# Wctrl-v1.net
KiCad netlist of a schematic drawn in Altium Designer
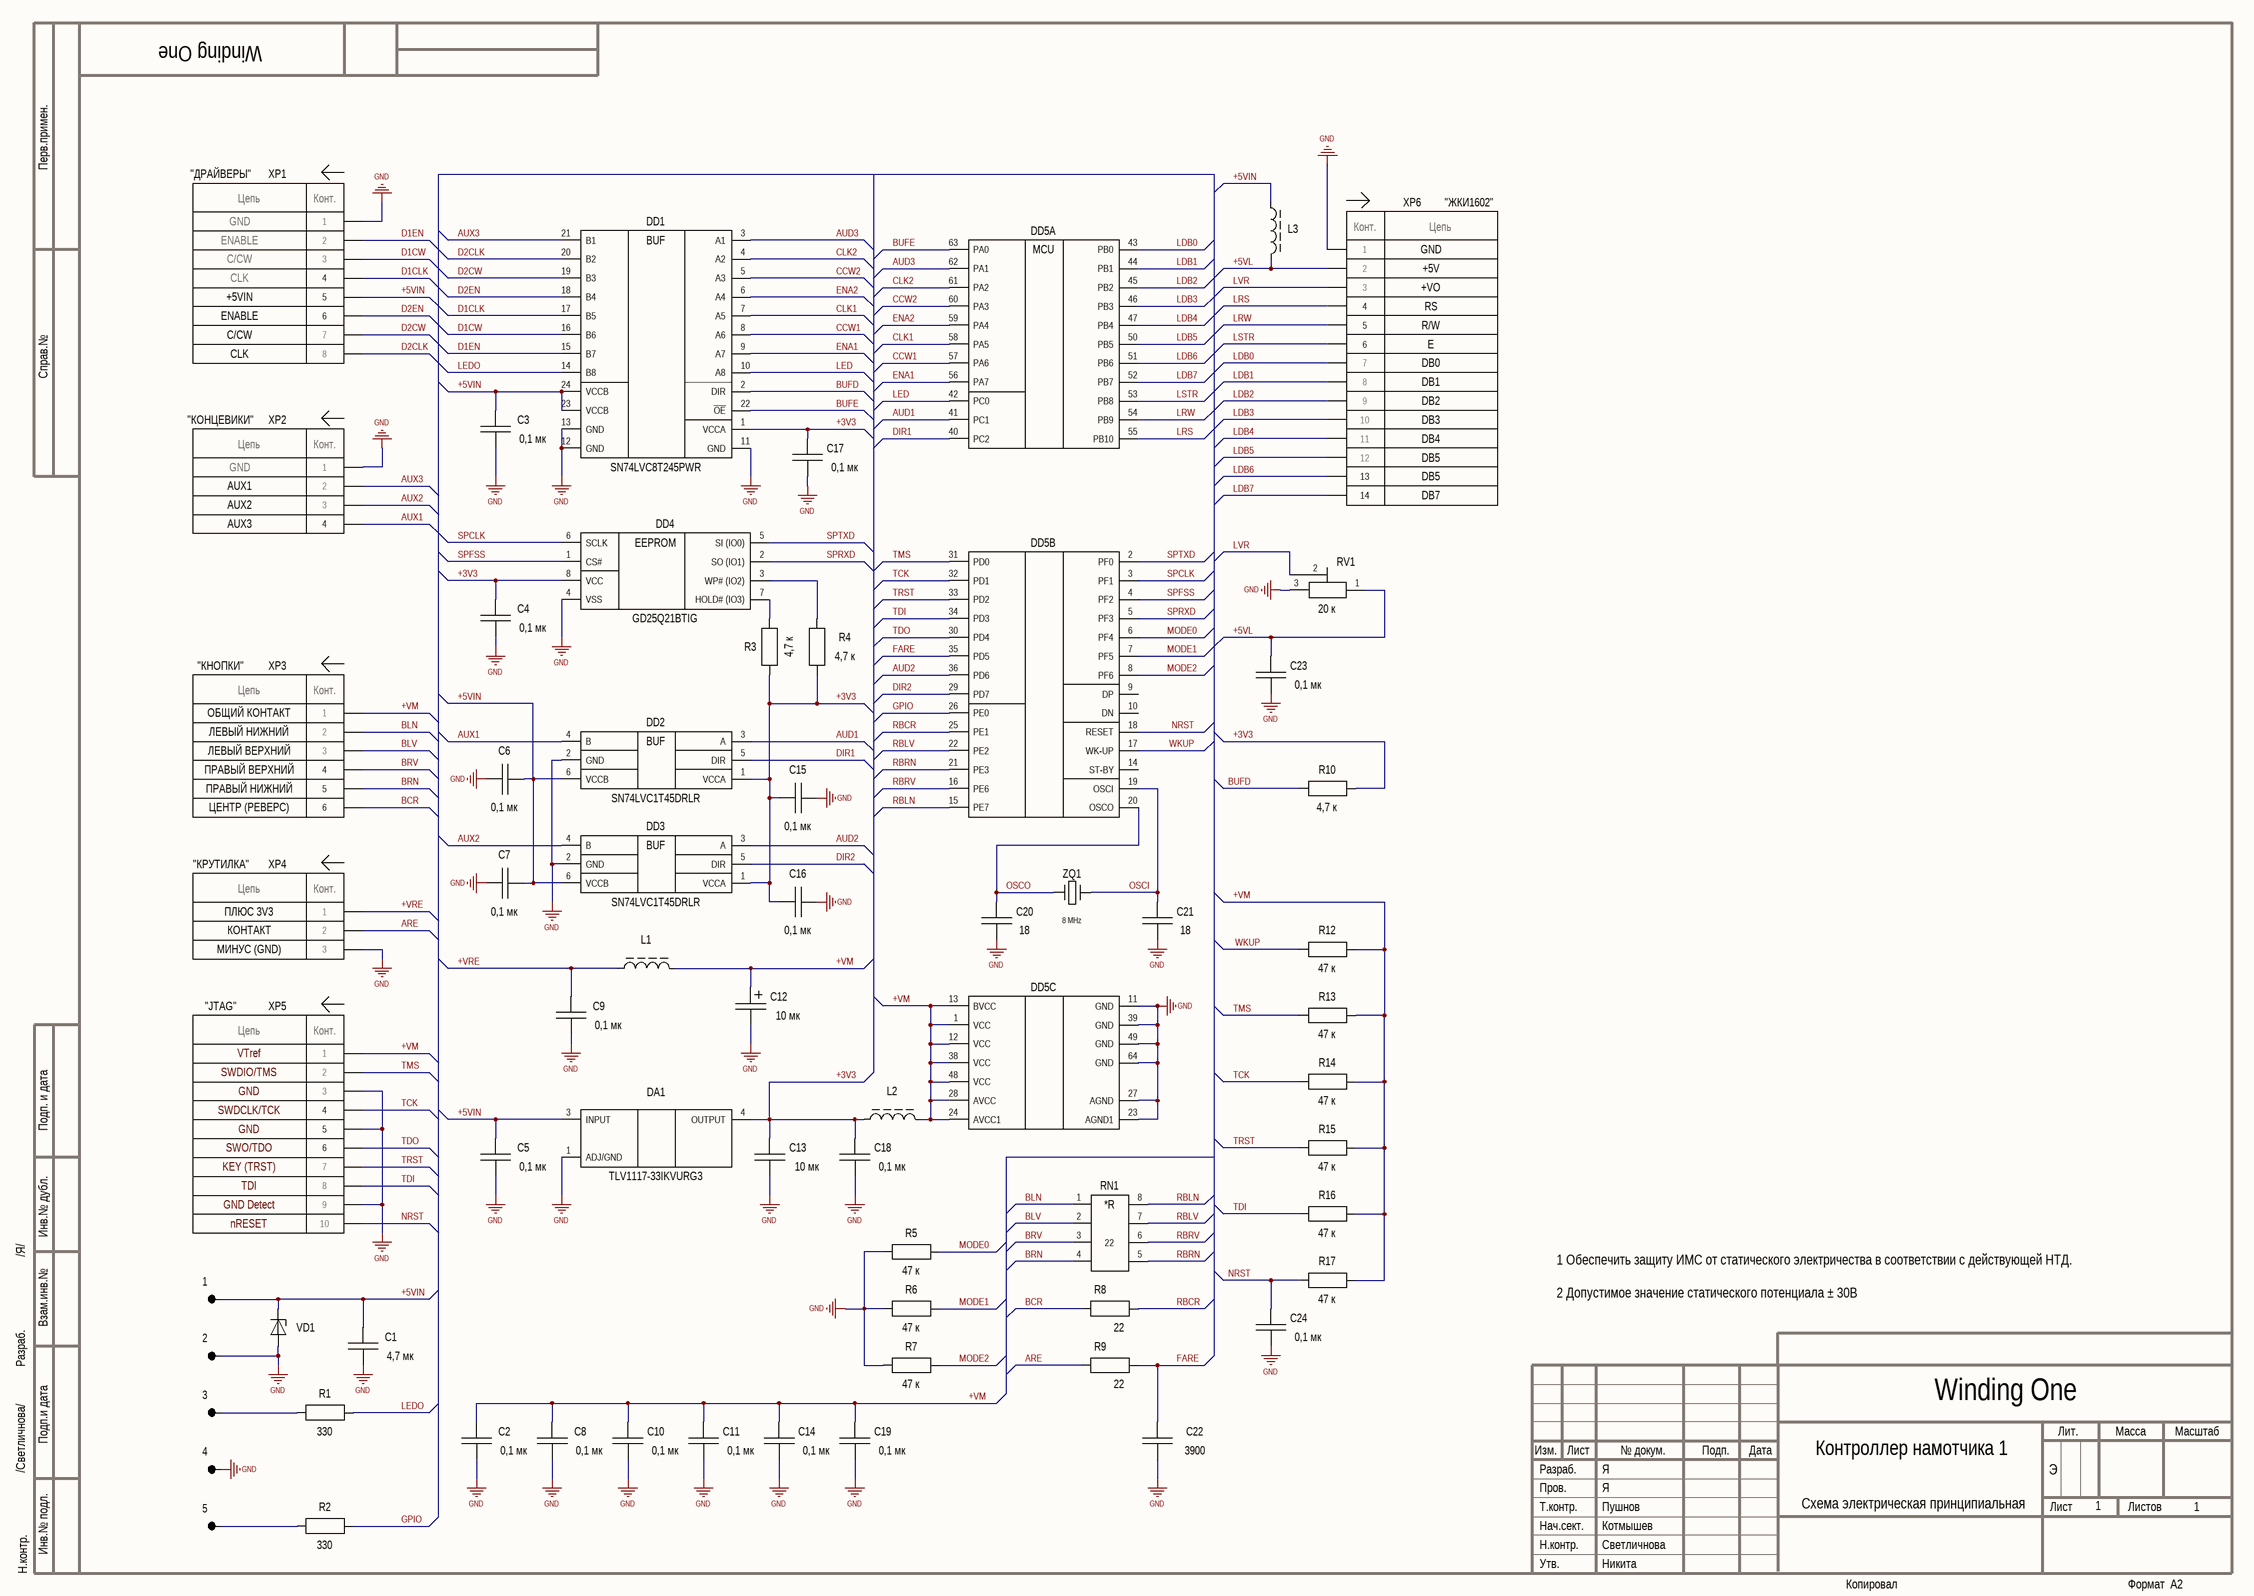
[diagram p0: Wctrl-v1.SchDoc]

(export (version "E")
  (design (tool "Eeschema 10.0.6"))
  (components
    (comp (ref "1")
      (value "Точка пайки")
      (footprint "Pad X 1.0 Round")
      (fields (field (name "PART NUMBER") "Точка п"))
      (libsource (lib "Altium_Base") (part "Точка пайки"))
    )
    (comp (ref "2")
      (value "Точка пайки")
      (footprint "Pad X 1.0 Round")
      (fields (field (name "PART NUMBER") "Точка п"))
      (libsource (lib "Altium_Base") (part "Точка пайки"))
    )
    (comp (ref "3")
      (value "Точка пайки")
      (footprint "Pad X 1.0 Round")
      (fields (field (name "PART NUMBER") "Точка п"))
      (libsource (lib "Altium_Base") (part "Точка пайки"))
    )
    (comp (ref "4")
      (value "Точка пайки")
      (footprint "Pad X 1.0 Round")
      (fields (field (name "PART NUMBER") "Точка п"))
      (libsource (lib "Altium_Base") (part "Точка пайки"))
    )
    (comp (ref "5")
      (value "Точка пайки")
      (footprint "Pad X 1.0 Round")
      (fields (field (name "PART NUMBER") "Точка п"))
      (libsource (lib "Altium_Base") (part "Точка пайки"))
    )
    (comp (ref "C1")
      (value "GRM31CR71E475K")
      (footprint "GRM31C R1")
      (description "10 мкФ ±10% X7R 25В, 1206 (3,2x1,6мм)")
      (fields (field (name "CAPACITANCE") "4,7 мк") (field (name "TOLERANCE") "±10%"))
      (libsource (lib "Altium_Base") (part "Конденсатор"))
    )
    (comp (ref "C2")
      (value "GRM21BR71H104K")
      (footprint "CAPC 0805 T1")
      (description "0,1 мкФ ±10% X7R 50В (2,0х1,25 мм)")
      (fields (field (name "CAPACITANCE") "0,1 мк") (field (name "TOLERANCE") "±10%"))
      (libsource (lib "Altium_Base") (part "Конденсатор"))
    )
    (comp (ref "C3")
      (value "GRM21BR71H104K")
      (footprint "CAPC 0805 T1")
      (description "0,1 мкФ ±10% X7R 50В (2,0х1,25 мм)")
      (fields (field (name "CAPACITANCE") "0,1 мк") (field (name "TOLERANCE") "±10%"))
      (libsource (lib "Altium_Base") (part "Конденсатор"))
    )
    (comp (ref "C4")
      (value "GRM21BR71H104K")
      (footprint "CAPC 0805 T1")
      (description "0,1 мкФ ±10% X7R 50В (2,0х1,25 мм)")
      (fields (field (name "CAPACITANCE") "0,1 мк") (field (name "TOLERANCE") "±10%"))
      (libsource (lib "Altium_Base") (part "Конденсатор"))
    )
    (comp (ref "C5")
      (value "GRM21BR71H104K")
      (footprint "CAPC 0805 T1")
      (description "0,1 мкФ ±10% X7R 50В (2,0х1,25 мм)")
      (fields (field (name "CAPACITANCE") "0,1 мк") (field (name "TOLERANCE") "±10%"))
      (libsource (lib "Altium_Base") (part "Конденсатор"))
    )
    (comp (ref "C6")
      (value "GRM21BR71H104K")
      (footprint "CAPC 0805 T1")
      (description "0,1 мкФ ±10% X7R 50В (2,0х1,25 мм)")
      (fields (field (name "CAPACITANCE") "0,1 мк") (field (name "TOLERANCE") "±10%"))
      (libsource (lib "Altium_Base") (part "Конденсатор"))
    )
    (comp (ref "C7")
      (value "GRM21BR71H104K")
      (footprint "CAPC 0805 T1")
      (description "0,1 мкФ ±10% X7R 50В (2,0х1,25 мм)")
      (fields (field (name "CAPACITANCE") "0,1 мк") (field (name "TOLERANCE") "±10%"))
      (libsource (lib "Altium_Base") (part "Конденсатор"))
    )
    (comp (ref "C8")
      (value "GRM21BR71H104K")
      (footprint "CAPC 0805 T1")
      (description "0,1 мкФ ±10% X7R 50В (2,0х1,25 мм)")
      (fields (field (name "CAPACITANCE") "0,1 мк") (field (name "TOLERANCE") "±10%"))
      (libsource (lib "Altium_Base") (part "Конденсатор"))
    )
    (comp (ref "C9")
      (value "GRM21BR71H104K")
      (footprint "CAPC 0805 T1")
      (description "0,1 мкФ ±10% X7R 50В (2,0х1,25 мм)")
      (fields (field (name "CAPACITANCE") "0,1 мк") (field (name "TOLERANCE") "±10%"))
      (libsource (lib "Altium_Base") (part "Конденсатор"))
    )
    (comp (ref "C10")
      (value "GRM21BR71H104K")
      (footprint "CAPC 0805 T1")
      (description "0,1 мкФ ±10% X7R 50В (2,0х1,25 мм)")
      (fields (field (name "CAPACITANCE") "0,1 мк") (field (name "TOLERANCE") "±10%"))
      (libsource (lib "Altium_Base") (part "Конденсатор"))
    )
    (comp (ref "C11")
      (value "GRM21BR71H104K")
      (footprint "CAPC 0805 T1")
      (description "0,1 мкФ ±10% X7R 50В (2,0х1,25 мм)")
      (fields (field (name "CAPACITANCE") "0,1 мк") (field (name "TOLERANCE") "±10%"))
      (libsource (lib "Altium_Base") (part "Конденсатор"))
    )
    (comp (ref "C12")
      (value "К53-68 \"C\"-20В-10 мкФ±10%")
      (footprint "К53-68-C")
      (description "Танталовый, тип C")
      (fields (field (name "CAPACITANCE") "10 мк") (field (name "TOLERANCE") "±10%"))
      (libsource (lib "Altium_Base") (part "Конд. полярный"))
    )
    (comp (ref "C13")
      (value "GRM31CR71C106K")
      (footprint "GRM31C R1")
      (description "10 мкФ, ±10% X7R 16В, 1206 (3,2x1,6x1,6 мм)")
      (fields (field (name "CAPACITANCE") "10 мк") (field (name "TOLERANCE") "±10%"))
      (libsource (lib "Altium_Base") (part "Конденсатор"))
    )
    (comp (ref "C14")
      (value "GRM21BR71H104K")
      (footprint "CAPC 0805 T1")
      (description "0,1 мкФ ±10% X7R 50В (2,0х1,25 мм)")
      (fields (field (name "CAPACITANCE") "0,1 мк") (field (name "TOLERANCE") "±10%"))
      (libsource (lib "Altium_Base") (part "Конденсатор"))
    )
    (comp (ref "C15")
      (value "GRM21BR71H104K")
      (footprint "CAPC 0805 T1")
      (description "0,1 мкФ ±10% X7R 50В (2,0х1,25 мм)")
      (fields (field (name "CAPACITANCE") "0,1 мк") (field (name "TOLERANCE") "±10%"))
      (libsource (lib "Altium_Base") (part "Конденсатор"))
    )
    (comp (ref "C16")
      (value "GRM21BR71H104K")
      (footprint "CAPC 0805 T1")
      (description "0,1 мкФ ±10% X7R 50В (2,0х1,25 мм)")
      (fields (field (name "CAPACITANCE") "0,1 мк") (field (name "TOLERANCE") "±10%"))
      (libsource (lib "Altium_Base") (part "Конденсатор"))
    )
    (comp (ref "C17")
      (value "GRM21BR71H104K")
      (footprint "CAPC 0805 T1")
      (description "0,1 мкФ ±10% X7R 50В (2,0х1,25 мм)")
      (fields (field (name "CAPACITANCE") "0,1 мк") (field (name "TOLERANCE") "±10%"))
      (libsource (lib "Altium_Base") (part "Конденсатор"))
    )
    (comp (ref "C18")
      (value "GRM21BR71H104K")
      (footprint "CAPC 0805 T1")
      (description "0,1 мкФ ±10% X7R 50В (2,0х1,25 мм)")
      (fields (field (name "CAPACITANCE") "0,1 мк") (field (name "TOLERANCE") "±10%"))
      (libsource (lib "Altium_Base") (part "Конденсатор"))
    )
    (comp (ref "C19")
      (value "GRM21BR71H104K")
      (footprint "CAPC 0805 T1")
      (description "0,1 мкФ ±10% X7R 50В (2,0х1,25 мм)")
      (fields (field (name "CAPACITANCE") "0,1 мк") (field (name "TOLERANCE") "±10%"))
      (libsource (lib "Altium_Base") (part "Конденсатор"))
    )
    (comp (ref "C20")
      (value "GRM1885C1H180J")
      (footprint "CAPC 0603 T1")
      (description "18 пФ ±5% C0G 50В (1,6x0,8мм)")
      (fields (field (name "CAPACITANCE") "18") (field (name "TOLERANCE") "±5%"))
      (libsource (lib "Altium_Base") (part "Конденсатор"))
    )
    (comp (ref "C21")
      (value "GRM1885C1H180J")
      (footprint "CAPC 0603 T1")
      (description "18 пФ ±5% C0G 50В (1,6x0,8мм)")
      (fields (field (name "CAPACITANCE") "18") (field (name "TOLERANCE") "±5%"))
      (libsource (lib "Altium_Base") (part "Конденсатор"))
    )
    (comp (ref "C22")
      (value "GRM2165C1H392J")
      (footprint "CAPC 0805 T1")
      (description "3900 пФ ±5% C0G 50В (2,0х1,25 мм)")
      (fields (field (name "CAPACITANCE") "3900") (field (name "TOLERANCE") "±5%"))
      (libsource (lib "Altium_Base") (part "Конденсатор"))
    )
    (comp (ref "C23")
      (value "GRM21BR71H104K")
      (footprint "CAPC 0805 T1")
      (description "0,1 мкФ ±10% X7R 50В (2,0х1,25 мм)")
      (fields (field (name "CAPACITANCE") "0,1 мк") (field (name "TOLERANCE") "±10%"))
      (libsource (lib "Altium_Base") (part "Конденсатор"))
    )
    (comp (ref "C24")
      (value "GRM21BR71H104K")
      (footprint "CAPC 0805 T1")
      (description "0,1 мкФ ±10% X7R 50В (2,0х1,25 мм)")
      (fields (field (name "CAPACITANCE") "0,1 мк") (field (name "TOLERANCE") "±10%"))
      (libsource (lib "Altium_Base") (part "Конденсатор"))
    )
    (comp (ref "DA1")
      (value "TLV1117-33IKVURG3")
      (footprint "TO-252_TI_KVU (KVU0003A)_R1")
      (description "3,3V Fixed Low-Dropout Voltage Regulator, TO-252")
      (libsource (lib "Altium_Base") (part "TLV1117-KVU"))
    )
    (comp (ref "DD1")
      (value "SN74LVC8T245PWR")
      (footprint "TSSOP24_TI_PW (PW0024A)")
      (description "Dual-Supply Bus Transceiver (8-bit) with 3-State Outputs, TSSOP-24")
      (libsource (lib "Altium_Base") (part "SN74LVC8T245"))
    )
    (comp (ref "DD2")
      (value "SN74LVC1T45DRLR")
      (footprint "SOT-5x3_TI_DRL(R-PDSO-N6)")
      (description "Single-Bit Dual-Supply Bus Transceiver With Configurable Voltage Translation and 3-State Outputs")
      (libsource (lib "Altium_Base") (part "SN74LVC1T45DRLR"))
    )
    (comp (ref "DD3")
      (value "SN74LVC1T45DRLR")
      (footprint "SOT-5x3_TI_DRL(R-PDSO-N6)")
      (description "Single-Bit Dual-Supply Bus Transceiver With Configurable Voltage Translation and 3-State Outputs")
      (libsource (lib "Altium_Base") (part "SN74LVC1T45DRLR"))
    )
    (comp (ref "DD4")
      (value "GD25Q21BTIG")
      (footprint "SOIC-8 IPC N")
      (description "Serial Flash 2M-bit, [SPI x 1 / x 2 / x 4], 3,3V, 104 MHz, SOP8")
      (libsource (lib "Altium_Base") (part "GD25Q21B"))
    )
    (comp (ref "DD5")
      (value "К1986ВЕ92QI")
      (footprint "К1986ВЕ92QI")
      (description "МК, 32-битное ядро ARM Cortex M3 80 МГц, LQFP64")
      (libsource (lib "Altium_Base") (part "К1986ВЕ92QI"))
    )
    (comp (ref "L1")
      (value "Дроссель BLM")
      (footprint "INDC2012X10N")
      (description "Chip Ferrite Bead BLM21_SN series - 200 mA, 470 Ohm (@100 MHz), 0805")
      (fields (field (name "PART NUMBER") "BLM21AG471SN1") (field (name "TOLERANCE") "25%"))
      (libsource (lib "Altium_Base") (part "Дроссель BLM"))
    )
    (comp (ref "L2")
      (value "Дроссель BLM")
      (footprint "INDC2012X10N")
      (description "Chip Ferrite Bead BLM21_SN series - 200 mA, 470 Ohm (@100 MHz), 0805")
      (fields (field (name "PART NUMBER") "BLM21AG471SN1") (field (name "TOLERANCE") "25%"))
      (libsource (lib "Altium_Base") (part "Дроссель BLM"))
    )
    (comp (ref "L3")
      (value "Дроссель BLM")
      (footprint "INDC2012X10N")
      (description "Chip Ferrite Bead BLM21_SN series - 200 mA, 470 Ohm (@100 MHz), 0805")
      (fields (field (name "PART NUMBER") "BLM21AG471SN1") (field (name "TOLERANCE") "25%"))
      (libsource (lib "Altium_Base") (part "Дроссель BLM"))
    )
    (comp (ref "R1")
      (value "Резистор")
      (footprint "IEC 2012N")
      (description "Чип-резистор 0805")
      (fields
        (field (name "PART NUMBER") "Р1-12-0,125-330 Ом±5%-Т")
        (field (name "RESISTANCE") "330")
        (field (name "TOLERANCE") "±5%")
      )
      (libsource (lib "Altium_Base") (part "Резистор"))
    )
    (comp (ref "R2")
      (value "Резистор")
      (footprint "IEC 2012N")
      (description "Чип-резистор 0805")
      (fields
        (field (name "PART NUMBER") "Р1-12-0,125-330 Ом±5%-Т")
        (field (name "RESISTANCE") "330")
        (field (name "TOLERANCE") "±5%")
      )
      (libsource (lib "Altium_Base") (part "Резистор"))
    )
    (comp (ref "R3")
      (value "Резистор")
      (footprint "IEC 2011N")
      (description "Чип-резистор 0603")
      (fields
        (field (name "PART NUMBER") "Р1-12-0,1-4,7 кОм±5%-Т")
        (field (name "RESISTANCE") "4,7 к")
        (field (name "TOLERANCE") "±5%")
      )
      (libsource (lib "Altium_Base") (part "Резистор"))
    )
    (comp (ref "R4")
      (value "Резистор")
      (footprint "IEC 2011N")
      (description "Чип-резистор 0603")
      (fields
        (field (name "PART NUMBER") "Р1-12-0,1-4,7 кОм±5%-Т")
        (field (name "RESISTANCE") "4,7 к")
        (field (name "TOLERANCE") "±5%")
      )
      (libsource (lib "Altium_Base") (part "Резистор"))
    )
    (comp (ref "R5")
      (value "Резистор")
      (footprint "IEC 2011N")
      (description "Чип-резистор 0603")
      (fields
        (field (name "PART NUMBER") "Р1-12-0,1-47 кОм±1%-М")
        (field (name "RESISTANCE") "47 к")
        (field (name "TOLERANCE") "±1%")
      )
      (libsource (lib "Altium_Base") (part "Резистор"))
    )
    (comp (ref "R6")
      (value "Резистор")
      (footprint "IEC 2011N")
      (description "Чип-резистор 0603")
      (fields
        (field (name "PART NUMBER") "Р1-12-0,1-47 кОм±1%-М")
        (field (name "RESISTANCE") "47 к")
        (field (name "TOLERANCE") "±1%")
      )
      (libsource (lib "Altium_Base") (part "Резистор"))
    )
    (comp (ref "R7")
      (value "Резистор")
      (footprint "IEC 2011N")
      (description "Чип-резистор 0603")
      (fields
        (field (name "PART NUMBER") "Р1-12-0,1-47 кОм±1%-М")
        (field (name "RESISTANCE") "47 к")
        (field (name "TOLERANCE") "±1%")
      )
      (libsource (lib "Altium_Base") (part "Резистор"))
    )
    (comp (ref "R8")
      (value "Резистор")
      (footprint "IEC 2011N")
      (description "Чип-резистор 0603")
      (fields
        (field (name "PART NUMBER") "Р1-12-0,1-22 Ом±5%-Т")
        (field (name "RESISTANCE") "22")
        (field (name "TOLERANCE") "±5%")
      )
      (libsource (lib "Altium_Base") (part "Резистор"))
    )
    (comp (ref "R9")
      (value "Резистор")
      (footprint "IEC 2011N")
      (description "Чип-резистор 0603")
      (fields
        (field (name "PART NUMBER") "Р1-12-0,1-22 Ом±5%-Т")
        (field (name "RESISTANCE") "22")
        (field (name "TOLERANCE") "±5%")
      )
      (libsource (lib "Altium_Base") (part "Резистор"))
    )
    (comp (ref "R10")
      (value "Резистор")
      (footprint "IEC 2011N")
      (description "Чип-резистор 0603")
      (fields
        (field (name "PART NUMBER") "Р1-12-0,1-4,7 кОм±5%-Т")
        (field (name "RESISTANCE") "4,7 к")
        (field (name "TOLERANCE") "±5%")
      )
      (libsource (lib "Altium_Base") (part "Резистор"))
    )
    (comp (ref "R12")
      (value "Резистор")
      (footprint "IEC 2011N")
      (description "Чип-резистор 0603")
      (fields
        (field (name "PART NUMBER") "Р1-12-0,1-47 кОм±1%-М")
        (field (name "RESISTANCE") "47 к")
        (field (name "TOLERANCE") "±1%")
      )
      (libsource (lib "Altium_Base") (part "Резистор"))
    )
    (comp (ref "R13")
      (value "Резистор")
      (footprint "IEC 2011N")
      (description "Чип-резистор 0603")
      (fields
        (field (name "PART NUMBER") "Р1-12-0,1-47 кОм±1%-М")
        (field (name "RESISTANCE") "47 к")
        (field (name "TOLERANCE") "±1%")
      )
      (libsource (lib "Altium_Base") (part "Резистор"))
    )
    (comp (ref "R14")
      (value "Резистор")
      (footprint "IEC 2011N")
      (description "Чип-резистор 0603")
      (fields
        (field (name "PART NUMBER") "Р1-12-0,1-47 кОм±1%-М")
        (field (name "RESISTANCE") "47 к")
        (field (name "TOLERANCE") "±1%")
      )
      (libsource (lib "Altium_Base") (part "Резистор"))
    )
    (comp (ref "R15")
      (value "Резистор")
      (footprint "IEC 2011N")
      (description "Чип-резистор 0603")
      (fields
        (field (name "PART NUMBER") "Р1-12-0,1-47 кОм±1%-М")
        (field (name "RESISTANCE") "47 к")
        (field (name "TOLERANCE") "±1%")
      )
      (libsource (lib "Altium_Base") (part "Резистор"))
    )
    (comp (ref "R16")
      (value "Резистор")
      (footprint "IEC 2011N")
      (description "Чип-резистор 0603")
      (fields
        (field (name "PART NUMBER") "Р1-12-0,1-47 кОм±1%-М")
        (field (name "RESISTANCE") "47 к")
        (field (name "TOLERANCE") "±1%")
      )
      (libsource (lib "Altium_Base") (part "Резистор"))
    )
    (comp (ref "R17")
      (value "Резистор")
      (footprint "IEC 2011N")
      (description "Чип-резистор 0603")
      (fields
        (field (name "PART NUMBER") "Р1-12-0,1-47 кОм±1%-М")
        (field (name "RESISTANCE") "47 к")
        (field (name "TOLERANCE") "±1%")
      )
      (libsource (lib "Altium_Base") (part "Резистор"))
    )
    (comp (ref "RN1")
      (value "CAT16-220J4LF")
      (footprint "НР1-2Р V1")
      (description "Набор резисторов 4шт х 22 Ом, 0,0625 Вт , 50В, 5%, SMD 3.2 x 1.6 x 0.8")
      (fields (field (name "RESISTANCE") "22") (field (name "TOLERANCE") "±5%"))
      (libsource (lib "Altium_Base") (part "Резиторов набор 8к"))
    )
    (comp (ref "RV1")
      (value "Резистор подстроечный")
      (footprint "3313J-1")
      (description "Trimming Potentiometer, 20 kOhm, SMD 3.5 x 3.2 x 2.2")
      (fields
        (field (name "PART NUMBER") "3313J-1-203E")
        (field (name "RESISTANCE") "20 к")
        (field (name "TOLERANCE") "±20%")
      )
      (libsource (lib "Altium_Base") (part "Резистор подстроечный"))
    )
    (comp (ref "VD1")
      (value "Стабилитрон")
      (footprint "SMBJ-LF-R1")
      (description "TVS Diode, Uni-directional, 12V, DO-214AA (SMB J-Bend)")
      (fields (field (name "PART NUMBER") "SMBJ12A"))
      (libsource (lib "Altium_Base") (part "Стабилитрон"))
    )
    (comp (ref "XP1")
      (value "X8 Connector XP")
      (footprint "СНП346-8ВП21-1")
      (description "Вилка СНП346 однорядная, прямая, 8 контактов")
      (fields (field (name "НАЗНАЧЕНИЕ") "\"ДРАЙВЕРЫ\"") (field (name "PART NUMBER") "СНП346-8ВП21-1-В"))
      (libsource (lib "Altium_Base") (part "X8 Connector XP"))
    )
    (comp (ref "XP2")
      (value "X4 Connector XP")
      (footprint "СНП346-4ВП21-1")
      (description "Вилка СНП346 однорядная, прямая, 4 контакта")
      (fields (field (name "НАЗНАЧЕНИЕ") "\"КОНЦЕВИКИ\"") (field (name "PART NUMBER") "СНП346-4ВП21-1-В"))
      (libsource (lib "Altium_Base") (part "X4 Connector XP"))
    )
    (comp (ref "XP3")
      (value "X6 Connector XP")
      (footprint "СНП346-6ВП21-1")
      (description "Вилка СНП346 однорядная, прямая, 6 контактов")
      (fields (field (name "НАЗНАЧЕНИЕ") "\"КНОПКИ\"") (field (name "PART NUMBER") "СНП346-6ВП21-1-В"))
      (libsource (lib "Altium_Base") (part "X6 Connector XP"))
    )
    (comp (ref "XP4")
      (value "X3 Connector XP")
      (footprint "СНП346-3ВП21-1")
      (description "Вилка СНП346 однорядная, прямая, 3 контакта")
      (fields (field (name "НАЗНАЧЕНИЕ") "\"КРУТИЛКА\"") (field (name "PART NUMBER") "СНП346-3ВП21-1-В"))
      (libsource (lib "Altium_Base") (part "X3 Connector XP"))
    )
    (comp (ref "XP5")
      (value "X10 Connector XP")
      (footprint "DS1014-10SF1B")
      (description "Вилка двухрядная на плату IDC-2-10, прямая, шаг 2  мм, 10 контактов")
      (fields (field (name "НАЗНАЧЕНИЕ") "\"JTAG\"") (field (name "PART NUMBER") "DS1014-10SF1B"))
      (libsource (lib "Altium_Base") (part "X10 Connector XP"))
    )
    (comp (ref "XP6")
      (value "X14 Connector XP")
      (footprint "DS1025-01-1X14")
      (description "Вилка на плату, прямая, шаг 2,0 мм, 14 контактов")
      (fields (field (name "НАЗНАЧЕНИЕ") "\"ЖКИ1602\"") (field (name "PART NUMBER") "DS1025-01*14P8BV2"))
      (libsource (lib "Altium_Base") (part "X14 Connector XP"))
    )
    (comp (ref "ZQ1")
      (value "Кварц 2к")
      (footprint "HC-49S AS TXC")
      (description "8.000 МHz (Tolerance ±30ppm, Stability ±50ppm, Load Capacitance 12 pF)")
      (fields (field (name "ЧАСТОТА") "8 MHz") (field (name "PART NUMBER") "AS-8.000MAGE"))
      (libsource (lib "Altium_Base") (part "Кварц 2к"))
    )
  )
  (nets
    (net (code "1") (name "/+3V3") (class "Default")
      (node (ref "C13") (pin "2") (pinfunction "2_2") (pintype "passive"))
      (node (ref "C15") (pin "2") (pinfunction "2_2") (pintype "passive"))
      (node (ref "C16") (pin "2") (pinfunction "2_2") (pintype "passive"))
      (node (ref "C17") (pin "2") (pinfunction "2_2") (pintype "passive"))
      (node (ref "C18") (pin "2") (pinfunction "2_2") (pintype "passive"))
      (node (ref "C4") (pin "2") (pinfunction "2_2") (pintype "passive"))
      (node (ref "DA1") (pin "4") (pinfunction "OUTPUT_4") (pintype "passive"))
      (node (ref "DD1") (pin "1") (pinfunction "VCCA_1") (pintype "passive"))
      (node (ref "DD2") (pin "1") (pinfunction "VCCA_1") (pintype "passive"))
      (node (ref "DD3") (pin "1") (pinfunction "VCCA_1") (pintype "passive"))
      (node (ref "DD4") (pin "8") (pinfunction "VCC_8") (pintype "passive"))
      (node (ref "L2") (pin "1") (pinfunction "1_1") (pintype "passive"))
      (node (ref "R10") (pin "2") (pinfunction "2_2") (pintype "passive"))
      (node (ref "R3") (pin "1") (pinfunction "1_1") (pintype "passive"))
      (node (ref "R4") (pin "1") (pinfunction "1_1") (pintype "passive"))
    )
    (net (code "2") (name "/+5VIN") (class "Default")
      (node (ref "1") (pin "1") (pinfunction "1_1") (pintype "passive"))
      (node (ref "C1") (pin "2") (pinfunction "2_2") (pintype "passive"))
      (node (ref "C3") (pin "2") (pinfunction "2_2") (pintype "passive"))
      (node (ref "C5") (pin "2") (pinfunction "2_2") (pintype "passive"))
      (node (ref "C6") (pin "1") (pinfunction "1_1") (pintype "passive"))
      (node (ref "C7") (pin "1") (pinfunction "1_1") (pintype "passive"))
      (node (ref "DA1") (pin "3") (pinfunction "INPUT_3") (pintype "passive"))
      (node (ref "DD1") (pin "23") (pinfunction "VCCB_23") (pintype "passive"))
      (node (ref "DD1") (pin "24") (pinfunction "VCCB_24") (pintype "passive"))
      (node (ref "DD2") (pin "6") (pinfunction "VCCB_6") (pintype "passive"))
      (node (ref "DD3") (pin "6") (pinfunction "VCCB_6") (pintype "passive"))
      (node (ref "L3") (pin "1") (pinfunction "1_1") (pintype "passive"))
      (node (ref "VD1") (pin "1") (pinfunction "Катод_1") (pintype "passive"))
      (node (ref "XP1") (pin "5") (pinfunction "5_5") (pintype "passive"))
    )
    (net (code "3") (name "/+5VL") (class "Default")
      (node (ref "C23") (pin "2") (pinfunction "2_2") (pintype "passive"))
      (node (ref "L3") (pin "2") (pinfunction "2_2") (pintype "passive"))
      (node (ref "RV1") (pin "1") (pinfunction "1_1") (pintype "passive"))
      (node (ref "XP6") (pin "2") (pinfunction "2_2") (pintype "passive"))
    )
    (net (code "4") (name "/+VM") (class "Default")
      (node (ref "C10") (pin "2") (pinfunction "2_2") (pintype "passive"))
      (node (ref "C11") (pin "2") (pinfunction "2_2") (pintype "passive"))
      (node (ref "C12") (pin "1") (pinfunction "1_1") (pintype "passive"))
      (node (ref "C14") (pin "2") (pinfunction "2_2") (pintype "passive"))
      (node (ref "C19") (pin "2") (pinfunction "2_2") (pintype "passive"))
      (node (ref "C2") (pin "2") (pinfunction "2_2") (pintype "passive"))
      (node (ref "C8") (pin "2") (pinfunction "2_2") (pintype "passive"))
      (node (ref "DD5") (pin "1") (pinfunction "VCC_1") (pintype "passive"))
      (node (ref "DD5") (pin "12") (pinfunction "VCC_12") (pintype "passive"))
      (node (ref "DD5") (pin "13") (pinfunction "BVCC_13") (pintype "passive"))
      (node (ref "DD5") (pin "24") (pinfunction "AVCC1_24") (pintype "passive"))
      (node (ref "DD5") (pin "28") (pinfunction "AVCC_28") (pintype "passive"))
      (node (ref "DD5") (pin "38") (pinfunction "VCC_38") (pintype "passive"))
      (node (ref "DD5") (pin "48") (pinfunction "VCC_48") (pintype "passive"))
      (node (ref "L1") (pin "2") (pinfunction "2_2") (pintype "passive"))
      (node (ref "L2") (pin "2") (pinfunction "2_2") (pintype "passive"))
      (node (ref "R12") (pin "2") (pinfunction "2_2") (pintype "passive"))
      (node (ref "R13") (pin "2") (pinfunction "2_2") (pintype "passive"))
      (node (ref "R14") (pin "2") (pinfunction "2_2") (pintype "passive"))
      (node (ref "R15") (pin "2") (pinfunction "2_2") (pintype "passive"))
      (node (ref "R16") (pin "2") (pinfunction "2_2") (pintype "passive"))
      (node (ref "R17") (pin "2") (pinfunction "2_2") (pintype "passive"))
      (node (ref "XP3") (pin "1") (pinfunction "1_1") (pintype "passive"))
      (node (ref "XP5") (pin "1") (pinfunction "1_1") (pintype "passive"))
    )
    (net (code "5") (name "/+VRE") (class "Default")
      (node (ref "C9") (pin "2") (pinfunction "2_2") (pintype "passive"))
      (node (ref "L1") (pin "1") (pinfunction "1_1") (pintype "passive"))
      (node (ref "XP4") (pin "1") (pinfunction "1_1") (pintype "passive"))
    )
    (net (code "6") (name "/ARE") (class "Default")
      (node (ref "R9") (pin "1") (pinfunction "1_1") (pintype "passive"))
      (node (ref "XP4") (pin "2") (pinfunction "2_2") (pintype "passive"))
    )
    (net (code "7") (name "/AUD1") (class "Default")
      (node (ref "DD2") (pin "3") (pinfunction "A_3") (pintype "passive"))
      (node (ref "DD5") (pin "41") (pinfunction "PC1_41") (pintype "passive"))
    )
    (net (code "8") (name "/AUD2") (class "Default")
      (node (ref "DD3") (pin "3") (pinfunction "A_3") (pintype "passive"))
      (node (ref "DD5") (pin "36") (pinfunction "PD6_36") (pintype "passive"))
    )
    (net (code "9") (name "/AUD3") (class "Default")
      (node (ref "DD1") (pin "3") (pinfunction "A1_3") (pintype "passive"))
      (node (ref "DD5") (pin "62") (pinfunction "PA1_62") (pintype "passive"))
    )
    (net (code "10") (name "/AUX1") (class "Default")
      (node (ref "DD2") (pin "4") (pinfunction "B_4") (pintype "passive"))
      (node (ref "XP2") (pin "4") (pinfunction "4_4") (pintype "passive"))
    )
    (net (code "11") (name "/AUX2") (class "Default")
      (node (ref "DD3") (pin "4") (pinfunction "B_4") (pintype "passive"))
      (node (ref "XP2") (pin "3") (pinfunction "3_3") (pintype "passive"))
    )
    (net (code "12") (name "/AUX3") (class "Default")
      (node (ref "DD1") (pin "21") (pinfunction "B1_21") (pintype "passive"))
      (node (ref "XP2") (pin "2") (pinfunction "2_2") (pintype "passive"))
    )
    (net (code "13") (name "/BCR") (class "Default")
      (node (ref "R8") (pin "1") (pinfunction "1_1") (pintype "passive"))
      (node (ref "XP3") (pin "6") (pinfunction "6_6") (pintype "passive"))
    )
    (net (code "14") (name "/BLN") (class "Default")
      (node (ref "RN1") (pin "1") (pintype "passive"))
      (node (ref "XP3") (pin "2") (pinfunction "2_2") (pintype "passive"))
    )
    (net (code "15") (name "/BLV") (class "Default")
      (node (ref "RN1") (pin "2") (pintype "passive"))
      (node (ref "XP3") (pin "3") (pinfunction "3_3") (pintype "passive"))
    )
    (net (code "16") (name "/BRN") (class "Default")
      (node (ref "RN1") (pin "4") (pintype "passive"))
      (node (ref "XP3") (pin "5") (pinfunction "5_5") (pintype "passive"))
    )
    (net (code "17") (name "/BRV") (class "Default")
      (node (ref "RN1") (pin "3") (pintype "passive"))
      (node (ref "XP3") (pin "4") (pinfunction "4_4") (pintype "passive"))
    )
    (net (code "18") (name "/BUFD") (class "Default")
      (node (ref "DD1") (pin "2") (pinfunction "DIR_2") (pintype "passive"))
      (node (ref "R10") (pin "1") (pinfunction "1_1") (pintype "passive"))
    )
    (net (code "19") (name "/BUFE") (class "Default")
      (node (ref "DD1") (pin "22") (pinfunction "~{OE}_22") (pintype "passive"))
      (node (ref "DD5") (pin "63") (pinfunction "PA0_63") (pintype "passive"))
    )
    (net (code "20") (name "/CCW1") (class "Default")
      (node (ref "DD1") (pin "8") (pinfunction "A6_8") (pintype "passive"))
      (node (ref "DD5") (pin "57") (pinfunction "PA6_57") (pintype "passive"))
    )
    (net (code "21") (name "/CCW2") (class "Default")
      (node (ref "DD1") (pin "5") (pinfunction "A3_5") (pintype "passive"))
      (node (ref "DD5") (pin "60") (pinfunction "PA3_60") (pintype "passive"))
    )
    (net (code "22") (name "/CLK1") (class "Default")
      (node (ref "DD1") (pin "7") (pinfunction "A5_7") (pintype "passive"))
      (node (ref "DD5") (pin "58") (pinfunction "PA5_58") (pintype "passive"))
    )
    (net (code "23") (name "/CLK2") (class "Default")
      (node (ref "DD1") (pin "4") (pinfunction "A2_4") (pintype "passive"))
      (node (ref "DD5") (pin "61") (pinfunction "PA2_61") (pintype "passive"))
    )
    (net (code "24") (name "/D1CLK") (class "Default")
      (node (ref "DD1") (pin "17") (pinfunction "B5_17") (pintype "passive"))
      (node (ref "XP1") (pin "4") (pinfunction "4_4") (pintype "passive"))
    )
    (net (code "25") (name "/D1CW") (class "Default")
      (node (ref "DD1") (pin "16") (pinfunction "B6_16") (pintype "passive"))
      (node (ref "XP1") (pin "3") (pinfunction "3_3") (pintype "passive"))
    )
    (net (code "26") (name "/D1EN") (class "Default")
      (node (ref "DD1") (pin "15") (pinfunction "B7_15") (pintype "passive"))
      (node (ref "XP1") (pin "2") (pinfunction "2_2") (pintype "passive"))
    )
    (net (code "27") (name "/D2CLK") (class "Default")
      (node (ref "DD1") (pin "20") (pinfunction "B2_20") (pintype "passive"))
      (node (ref "XP1") (pin "8") (pinfunction "8_8") (pintype "passive"))
    )
    (net (code "28") (name "/D2CW") (class "Default")
      (node (ref "DD1") (pin "19") (pinfunction "B3_19") (pintype "passive"))
      (node (ref "XP1") (pin "7") (pinfunction "7_7") (pintype "passive"))
    )
    (net (code "29") (name "/D2EN") (class "Default")
      (node (ref "DD1") (pin "18") (pinfunction "B4_18") (pintype "passive"))
      (node (ref "XP1") (pin "6") (pinfunction "6_6") (pintype "passive"))
    )
    (net (code "30") (name "/DIR1") (class "Default")
      (node (ref "DD2") (pin "5") (pinfunction "DIR_5") (pintype "passive"))
      (node (ref "DD5") (pin "40") (pinfunction "PC2_40") (pintype "passive"))
    )
    (net (code "31") (name "/DIR2") (class "Default")
      (node (ref "DD3") (pin "5") (pinfunction "DIR_5") (pintype "passive"))
      (node (ref "DD5") (pin "29") (pinfunction "PD7_29") (pintype "passive"))
    )
    (net (code "32") (name "/ENA1") (class "Default")
      (node (ref "DD1") (pin "9") (pinfunction "A7_9") (pintype "passive"))
      (node (ref "DD5") (pin "56") (pinfunction "PA7_56") (pintype "passive"))
    )
    (net (code "33") (name "/ENA2") (class "Default")
      (node (ref "DD1") (pin "6") (pinfunction "A4_6") (pintype "passive"))
      (node (ref "DD5") (pin "59") (pinfunction "PA4_59") (pintype "passive"))
    )
    (net (code "34") (name "/FARE") (class "Default")
      (node (ref "C22") (pin "2") (pinfunction "2_2") (pintype "passive"))
      (node (ref "DD5") (pin "35") (pinfunction "PD5_35") (pintype "passive"))
      (node (ref "R9") (pin "2") (pinfunction "2_2") (pintype "passive"))
    )
    (net (code "35") (name "/GPIO") (class "Default")
      (node (ref "DD5") (pin "26") (pinfunction "PE0_26") (pintype "passive"))
      (node (ref "R2") (pin "2") (pinfunction "2_2") (pintype "passive"))
    )
    (net (code "36") (name "/LDB0") (class "Default")
      (node (ref "DD5") (pin "43") (pinfunction "PB0_43") (pintype "passive"))
      (node (ref "XP6") (pin "7") (pinfunction "7_7") (pintype "passive"))
    )
    (net (code "37") (name "/LDB1") (class "Default")
      (node (ref "DD5") (pin "44") (pinfunction "PB1_44") (pintype "passive"))
      (node (ref "XP6") (pin "8") (pinfunction "8_8") (pintype "passive"))
    )
    (net (code "38") (name "/LDB2") (class "Default")
      (node (ref "DD5") (pin "45") (pinfunction "PB2_45") (pintype "passive"))
      (node (ref "XP6") (pin "9") (pinfunction "9_9") (pintype "passive"))
    )
    (net (code "39") (name "/LDB3") (class "Default")
      (node (ref "DD5") (pin "46") (pinfunction "PB3_46") (pintype "passive"))
      (node (ref "XP6") (pin "10") (pinfunction "10_10") (pintype "passive"))
    )
    (net (code "40") (name "/LDB4") (class "Default")
      (node (ref "DD5") (pin "47") (pinfunction "PB4_47") (pintype "passive"))
      (node (ref "XP6") (pin "11") (pinfunction "11_11") (pintype "passive"))
    )
    (net (code "41") (name "/LDB5") (class "Default")
      (node (ref "DD5") (pin "50") (pinfunction "PB5_50") (pintype "passive"))
      (node (ref "XP6") (pin "12") (pinfunction "12_12") (pintype "passive"))
    )
    (net (code "42") (name "/LDB6") (class "Default")
      (node (ref "DD5") (pin "51") (pinfunction "PB6_51") (pintype "passive"))
      (node (ref "XP6") (pin "13") (pinfunction "13_13") (pintype "passive"))
    )
    (net (code "43") (name "/LDB7") (class "Default")
      (node (ref "DD5") (pin "52") (pinfunction "PB7_52") (pintype "passive"))
      (node (ref "XP6") (pin "14") (pinfunction "14_14") (pintype "passive"))
    )
    (net (code "44") (name "/LED") (class "Default")
      (node (ref "DD1") (pin "10") (pinfunction "A8_10") (pintype "passive"))
      (node (ref "DD5") (pin "42") (pinfunction "PC0_42") (pintype "passive"))
    )
    (net (code "45") (name "/LEDO") (class "Default")
      (node (ref "DD1") (pin "14") (pinfunction "B8_14") (pintype "passive"))
      (node (ref "R1") (pin "2") (pinfunction "2_2") (pintype "passive"))
    )
    (net (code "46") (name "/LRS") (class "Default")
      (node (ref "DD5") (pin "55") (pinfunction "PB10_55") (pintype "passive"))
      (node (ref "XP6") (pin "4") (pinfunction "4_4") (pintype "passive"))
    )
    (net (code "47") (name "/LRW") (class "Default")
      (node (ref "DD5") (pin "54") (pinfunction "PB9_54") (pintype "passive"))
      (node (ref "XP6") (pin "5") (pinfunction "5_5") (pintype "passive"))
    )
    (net (code "48") (name "/LSTR") (class "Default")
      (node (ref "DD5") (pin "53") (pinfunction "PB8_53") (pintype "passive"))
      (node (ref "XP6") (pin "6") (pinfunction "6_6") (pintype "passive"))
    )
    (net (code "49") (name "/LVR") (class "Default")
      (node (ref "RV1") (pin "2") (pinfunction "2_2") (pintype "passive"))
      (node (ref "XP6") (pin "3") (pinfunction "3_3") (pintype "passive"))
    )
    (net (code "50") (name "/MODE0") (class "Default")
      (node (ref "DD5") (pin "6") (pinfunction "PF4_6") (pintype "passive"))
      (node (ref "R5") (pin "2") (pinfunction "2_2") (pintype "passive"))
    )
    (net (code "51") (name "/MODE1") (class "Default")
      (node (ref "DD5") (pin "7") (pinfunction "PF5_7") (pintype "passive"))
      (node (ref "R6") (pin "2") (pinfunction "2_2") (pintype "passive"))
    )
    (net (code "52") (name "/MODE2") (class "Default")
      (node (ref "DD5") (pin "8") (pinfunction "PF6_8") (pintype "passive"))
      (node (ref "R7") (pin "2") (pinfunction "2_2") (pintype "passive"))
    )
    (net (code "53") (name "/NRST") (class "Default")
      (node (ref "C24") (pin "2") (pinfunction "2_2") (pintype "passive"))
      (node (ref "DD5") (pin "18") (pinfunction "RESET_18") (pintype "passive"))
      (node (ref "R17") (pin "1") (pinfunction "1_1") (pintype "passive"))
      (node (ref "XP5") (pin "10") (pinfunction "10_10") (pintype "passive"))
    )
    (net (code "54") (name "/OSCI") (class "Default")
      (node (ref "C21") (pin "2") (pinfunction "2_2") (pintype "passive"))
      (node (ref "DD5") (pin "19") (pinfunction "OSCI_19") (pintype "passive"))
      (node (ref "ZQ1") (pin "2") (pinfunction "2_2") (pintype "passive"))
    )
    (net (code "55") (name "/OSCO") (class "Default")
      (node (ref "C20") (pin "2") (pinfunction "2_2") (pintype "passive"))
      (node (ref "DD5") (pin "20") (pinfunction "OSCO_20") (pintype "passive"))
      (node (ref "ZQ1") (pin "1") (pinfunction "1_1") (pintype "passive"))
    )
    (net (code "56") (name "/RBCR") (class "Default")
      (node (ref "DD5") (pin "25") (pinfunction "PE1_25") (pintype "passive"))
      (node (ref "R8") (pin "2") (pinfunction "2_2") (pintype "passive"))
    )
    (net (code "57") (name "/RBLN") (class "Default")
      (node (ref "DD5") (pin "15") (pinfunction "PE7_15") (pintype "passive"))
      (node (ref "RN1") (pin "8") (pintype "passive"))
    )
    (net (code "58") (name "/RBLV") (class "Default")
      (node (ref "DD5") (pin "22") (pinfunction "PE2_22") (pintype "passive"))
      (node (ref "RN1") (pin "7") (pintype "passive"))
    )
    (net (code "59") (name "/RBRN") (class "Default")
      (node (ref "DD5") (pin "21") (pinfunction "PE3_21") (pintype "passive"))
      (node (ref "RN1") (pin "5") (pintype "passive"))
    )
    (net (code "60") (name "/RBRV") (class "Default")
      (node (ref "DD5") (pin "16") (pinfunction "PE6_16") (pintype "passive"))
      (node (ref "RN1") (pin "6") (pintype "passive"))
    )
    (net (code "61") (name "/SPCLK") (class "Default")
      (node (ref "DD4") (pin "6") (pinfunction "SCLK_6") (pintype "passive"))
      (node (ref "DD5") (pin "3") (pinfunction "PF1_3") (pintype "passive"))
    )
    (net (code "62") (name "/SPFSS") (class "Default")
      (node (ref "DD4") (pin "1") (pinfunction "CS#_1") (pintype "passive"))
      (node (ref "DD5") (pin "4") (pinfunction "PF2_4") (pintype "passive"))
    )
    (net (code "63") (name "/SPRXD") (class "Default")
      (node (ref "DD4") (pin "2") (pinfunction "SO_(IO1)_2") (pintype "passive"))
      (node (ref "DD5") (pin "5") (pinfunction "PF3_5") (pintype "passive"))
    )
    (net (code "64") (name "/SPTXD") (class "Default")
      (node (ref "DD4") (pin "5") (pinfunction "SI_(IO0)_5") (pintype "passive"))
      (node (ref "DD5") (pin "2") (pinfunction "PF0_2") (pintype "passive"))
    )
    (net (code "65") (name "/TCK") (class "Default")
      (node (ref "DD5") (pin "32") (pinfunction "PD1_32") (pintype "passive"))
      (node (ref "R14") (pin "1") (pinfunction "1_1") (pintype "passive"))
      (node (ref "XP5") (pin "4") (pinfunction "4_4") (pintype "passive"))
    )
    (net (code "66") (name "/TDI") (class "Default")
      (node (ref "DD5") (pin "34") (pinfunction "PD3_34") (pintype "passive"))
      (node (ref "R16") (pin "1") (pinfunction "1_1") (pintype "passive"))
      (node (ref "XP5") (pin "8") (pinfunction "8_8") (pintype "passive"))
    )
    (net (code "67") (name "/TDO") (class "Default")
      (node (ref "DD5") (pin "30") (pinfunction "PD4_30") (pintype "passive"))
      (node (ref "XP5") (pin "6") (pinfunction "6_6") (pintype "passive"))
    )
    (net (code "68") (name "/TMS") (class "Default")
      (node (ref "DD5") (pin "31") (pinfunction "PD0_31") (pintype "passive"))
      (node (ref "R13") (pin "1") (pinfunction "1_1") (pintype "passive"))
      (node (ref "XP5") (pin "2") (pinfunction "2_2") (pintype "passive"))
    )
    (net (code "69") (name "/TRST") (class "Default")
      (node (ref "DD5") (pin "33") (pinfunction "PD2_33") (pintype "passive"))
      (node (ref "R15") (pin "1") (pinfunction "1_1") (pintype "passive"))
      (node (ref "XP5") (pin "7") (pinfunction "7_7") (pintype "passive"))
    )
    (net (code "70") (name "/WKUP") (class "Default")
      (node (ref "DD5") (pin "17") (pinfunction "WK-UP_17") (pintype "passive"))
      (node (ref "R12") (pin "1") (pinfunction "1_1") (pintype "passive"))
    )
    (net (code "71") (name "GND") (class "Default")
      (node (ref "2") (pin "1") (pinfunction "1_1") (pintype "passive"))
      (node (ref "4") (pin "1") (pinfunction "1_1") (pintype "passive"))
      (node (ref "C1") (pin "1") (pinfunction "1_1") (pintype "passive"))
      (node (ref "C10") (pin "1") (pinfunction "1_1") (pintype "passive"))
      (node (ref "C11") (pin "1") (pinfunction "1_1") (pintype "passive"))
      (node (ref "C12") (pin "2") (pinfunction "2_2") (pintype "passive"))
      (node (ref "C13") (pin "1") (pinfunction "1_1") (pintype "passive"))
      (node (ref "C14") (pin "1") (pinfunction "1_1") (pintype "passive"))
      (node (ref "C15") (pin "1") (pinfunction "1_1") (pintype "passive"))
      (node (ref "C16") (pin "1") (pinfunction "1_1") (pintype "passive"))
      (node (ref "C17") (pin "1") (pinfunction "1_1") (pintype "passive"))
      (node (ref "C18") (pin "1") (pinfunction "1_1") (pintype "passive"))
      (node (ref "C19") (pin "1") (pinfunction "1_1") (pintype "passive"))
      (node (ref "C2") (pin "1") (pinfunction "1_1") (pintype "passive"))
      (node (ref "C20") (pin "1") (pinfunction "1_1") (pintype "passive"))
      (node (ref "C21") (pin "1") (pinfunction "1_1") (pintype "passive"))
      (node (ref "C22") (pin "1") (pinfunction "1_1") (pintype "passive"))
      (node (ref "C23") (pin "1") (pinfunction "1_1") (pintype "passive"))
      (node (ref "C24") (pin "1") (pinfunction "1_1") (pintype "passive"))
      (node (ref "C3") (pin "1") (pinfunction "1_1") (pintype "passive"))
      (node (ref "C4") (pin "1") (pinfunction "1_1") (pintype "passive"))
      (node (ref "C5") (pin "1") (pinfunction "1_1") (pintype "passive"))
      (node (ref "C6") (pin "2") (pinfunction "2_2") (pintype "passive"))
      (node (ref "C7") (pin "2") (pinfunction "2_2") (pintype "passive"))
      (node (ref "C8") (pin "1") (pinfunction "1_1") (pintype "passive"))
      (node (ref "C9") (pin "1") (pinfunction "1_1") (pintype "passive"))
      (node (ref "DA1") (pin "1") (pinfunction "ADJ/GND_1") (pintype "passive"))
      (node (ref "DD1") (pin "11") (pinfunction "GND_11") (pintype "passive"))
      (node (ref "DD1") (pin "12") (pinfunction "GND_12") (pintype "passive"))
      (node (ref "DD1") (pin "13") (pinfunction "GND_13") (pintype "passive"))
      (node (ref "DD2") (pin "2") (pinfunction "GND_2") (pintype "passive"))
      (node (ref "DD3") (pin "2") (pinfunction "GND_2") (pintype "passive"))
      (node (ref "DD4") (pin "4") (pinfunction "VSS_4") (pintype "passive"))
      (node (ref "DD5") (pin "11") (pinfunction "GND_11") (pintype "passive"))
      (node (ref "DD5") (pin "23") (pinfunction "AGND1_23") (pintype "passive"))
      (node (ref "DD5") (pin "27") (pinfunction "AGND_27") (pintype "passive"))
      (node (ref "DD5") (pin "39") (pinfunction "GND_39") (pintype "passive"))
      (node (ref "DD5") (pin "49") (pinfunction "GND_49") (pintype "passive"))
      (node (ref "DD5") (pin "64") (pinfunction "GND_64") (pintype "passive"))
      (node (ref "R5") (pin "1") (pinfunction "1_1") (pintype "passive"))
      (node (ref "R6") (pin "1") (pinfunction "1_1") (pintype "passive"))
      (node (ref "R7") (pin "1") (pinfunction "1_1") (pintype "passive"))
      (node (ref "RV1") (pin "3") (pinfunction "3_3") (pintype "passive"))
      (node (ref "VD1") (pin "2") (pinfunction "Анод_2") (pintype "passive"))
      (node (ref "XP1") (pin "1") (pinfunction "1_1") (pintype "passive"))
      (node (ref "XP2") (pin "1") (pinfunction "1_1") (pintype "passive"))
      (node (ref "XP4") (pin "3") (pinfunction "3_3") (pintype "passive"))
      (node (ref "XP5") (pin "3") (pinfunction "3_3") (pintype "passive"))
      (node (ref "XP5") (pin "5") (pinfunction "5_5") (pintype "passive"))
      (node (ref "XP5") (pin "9") (pinfunction "9_9") (pintype "passive"))
      (node (ref "XP6") (pin "1") (pinfunction "1_1") (pintype "passive"))
    )
    (net (code "72") (name "Net-(3-Pad1)") (class "Default")
      (node (ref "3") (pin "1") (pinfunction "1_1") (pintype "passive"))
      (node (ref "R1") (pin "1") (pinfunction "1_1") (pintype "passive"))
    )
    (net (code "73") (name "Net-(5-Pad1)") (class "Default")
      (node (ref "5") (pin "1") (pinfunction "1_1") (pintype "passive"))
      (node (ref "R2") (pin "1") (pinfunction "1_1") (pintype "passive"))
    )
    (net (code "74") (name "Net-(DD4-HOLD#_(IO3))") (class "Default")
      (node (ref "DD4") (pin "7") (pinfunction "HOLD#_(IO3)_7") (pintype "passive"))
      (node (ref "R3") (pin "2") (pinfunction "2_2") (pintype "passive"))
    )
    (net (code "75") (name "Net-(DD4-WP#_(IO2))") (class "Default")
      (node (ref "DD4") (pin "3") (pinfunction "WP#_(IO2)_3") (pintype "passive"))
      (node (ref "R4") (pin "2") (pinfunction "2_2") (pintype "passive"))
    )
    (net (code "76") (name "unconnected-(DD5B-DN-Pad10)") (class "Default")
      (node (ref "DD5") (pin "10") (pinfunction "DN_10") (pintype "passive"))
    )
    (net (code "77") (name "unconnected-(DD5B-DP-Pad9)") (class "Default")
      (node (ref "DD5") (pin "9") (pinfunction "DP_9") (pintype "passive"))
    )
    (net (code "78") (name "unconnected-(DD5B-ST-BY-Pad14)") (class "Default")
      (node (ref "DD5") (pin "14") (pinfunction "ST-BY_14") (pintype "passive"))
    )
  )
)
